# MelansonTech_Isolated_Shunt_Amplifier_re.net
KiCad netlist of a schematic drawn in Altium Designer
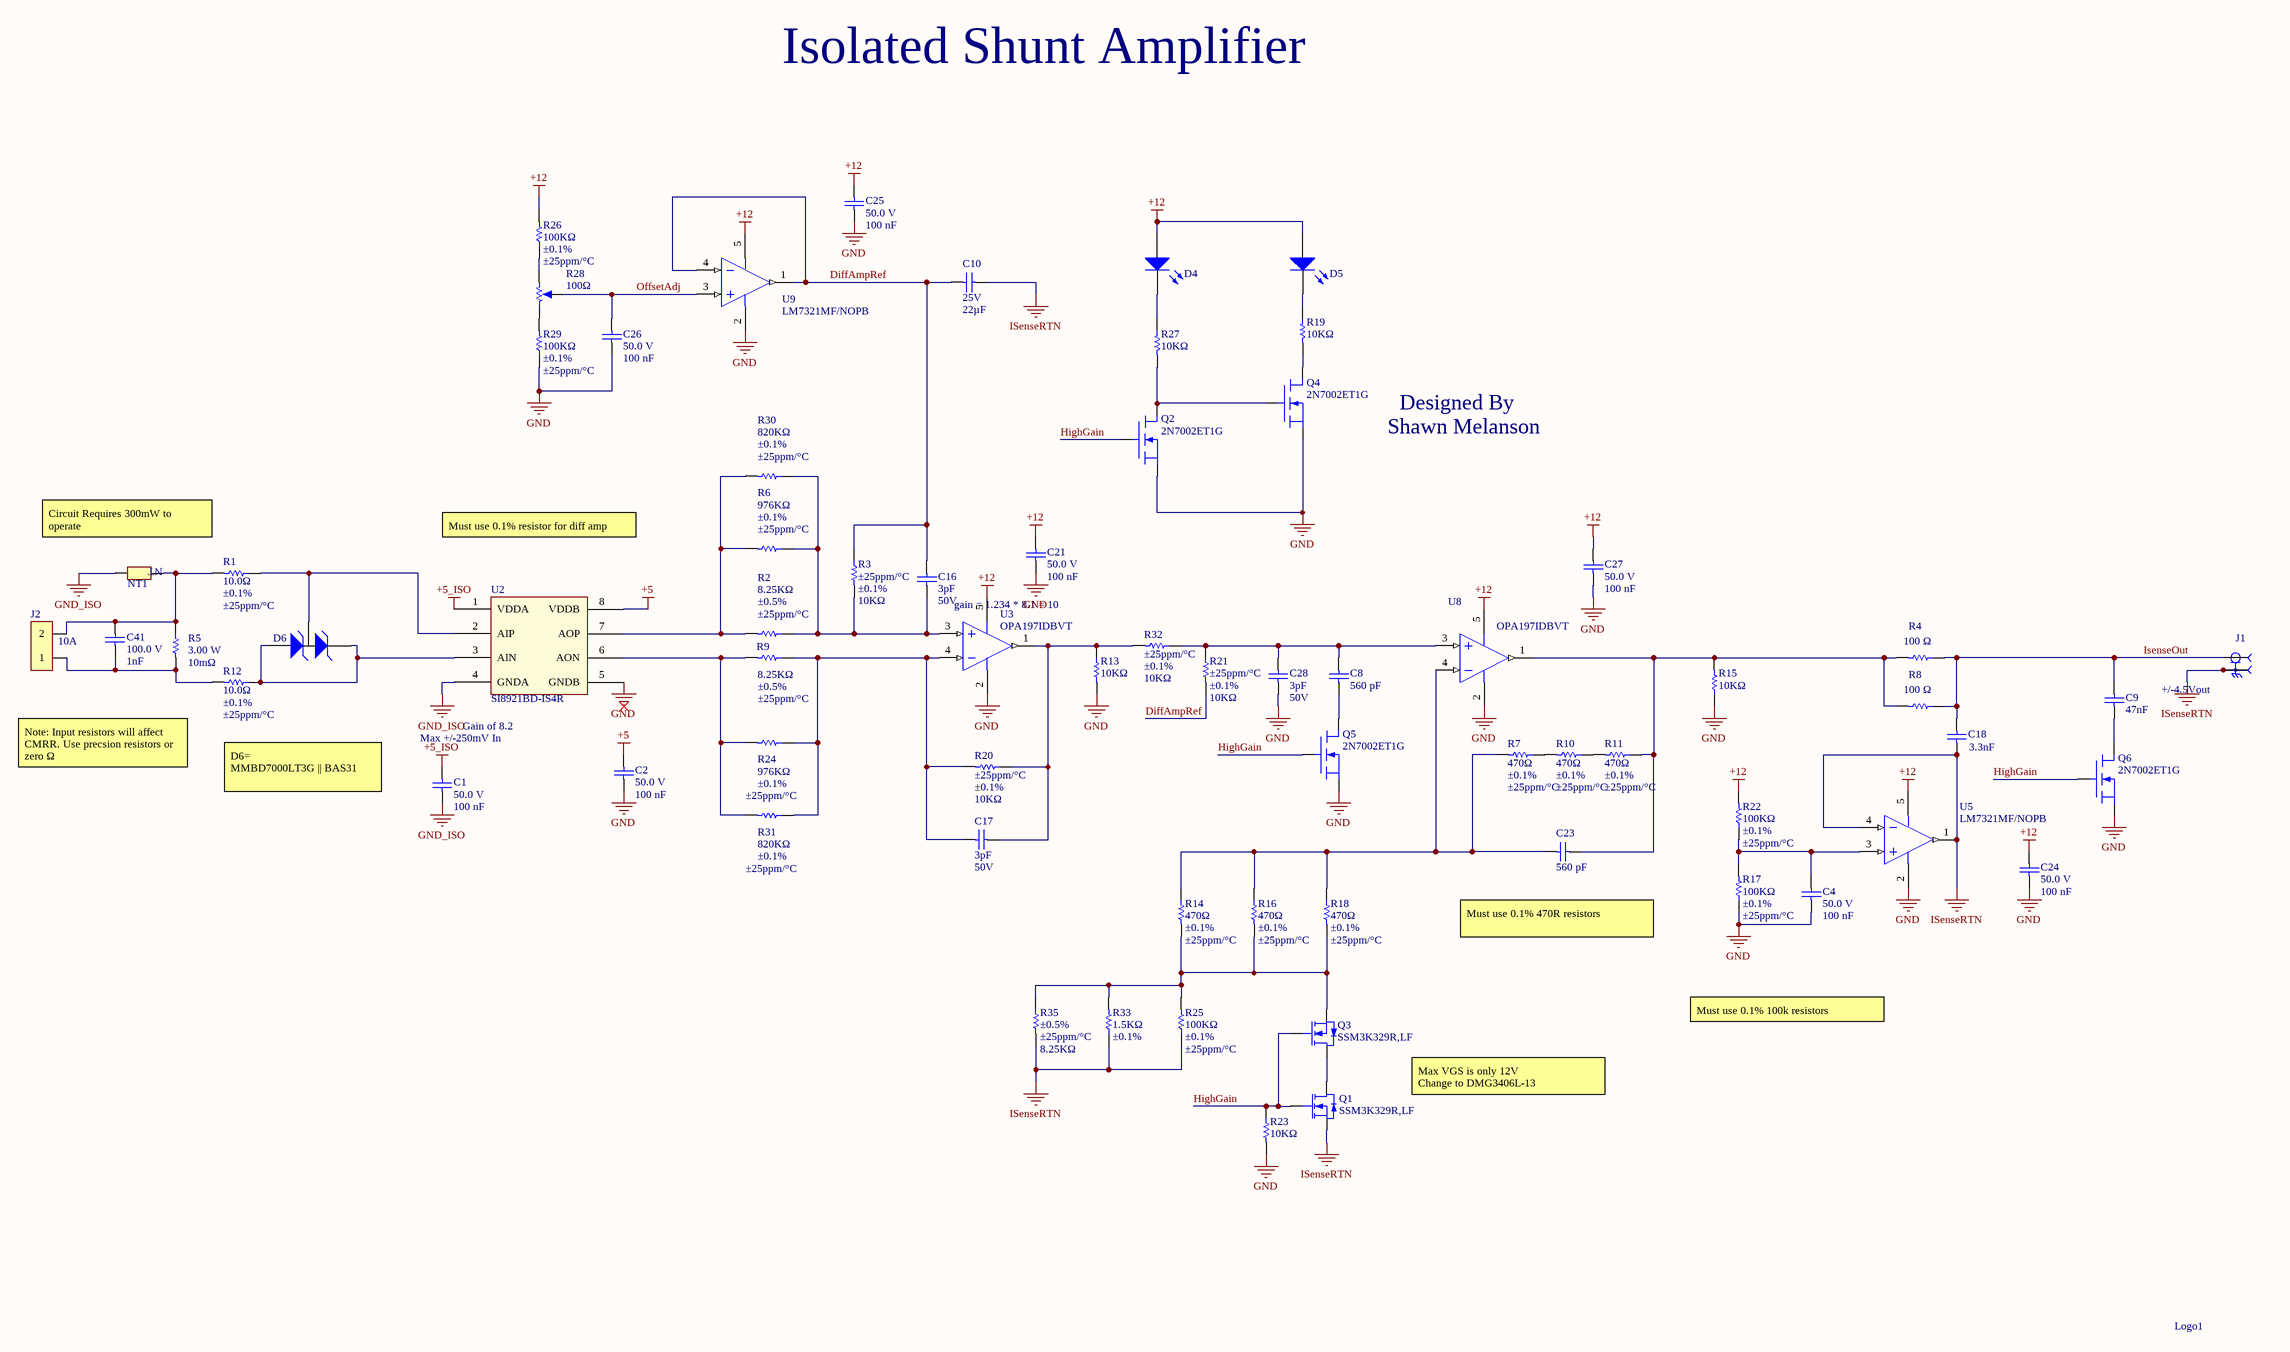
[diagram p0: MelansonTech Isolated Shunt Amplifier rev 2.SchDoc]

(export (version "E")
  (design (tool "Eeschema 10.0.6"))
  (components
    (comp (ref "C1")
      (value "CC0805KRX7R9BB104")
      (footprint "CAP, 0805, HD")
      (description "CAP CER 0.1UF 50V X7R 0805")
      (fields
        (field (name "VOLTAGE RATING (DC)") "50.0 V")
        (field (name "CAPACITANCE") "100 nF")
        (field (name "MANUFACTURER") "YAGEO")
      )
      (libsource (lib "Master Mar2024") (part "Cap,0805,100nf,50V,5%,CC0805KRX7R9BB104"))
    )
    (comp (ref "C2")
      (value "CC0805KRX7R9BB104")
      (footprint "CAP, 0805, HD")
      (description "CAP CER 0.1UF 50V X7R 0805")
      (fields
        (field (name "VOLTAGE RATING (DC)") "50.0 V")
        (field (name "CAPACITANCE") "100 nF")
        (field (name "MANUFACTURER") "YAGEO")
      )
      (libsource (lib "Master Mar2024") (part "Cap,0805,100nf,50V,5%,CC0805KRX7R9BB104"))
    )
    (comp (ref "C4")
      (value "CC0805KRX7R9BB104")
      (footprint "CAP, 0805, HD")
      (description "CAP CER 0.1UF 50V X7R 0805")
      (fields
        (field (name "VOLTAGE RATING (DC)") "50.0 V")
        (field (name "CAPACITANCE") "100 nF")
        (field (name "MANUFACTURER") "YAGEO")
      )
      (libsource (lib "Master Mar2024") (part "Cap,0805,100nf,50V,5%,CC0805KRX7R9BB104"))
    )
    (comp (ref "C8")
      (value "CC0805JRNPO9BN561")
      (footprint "CAP, 0805, HD")
      (description "CAP CER 560PF 50V C0G/NPO 0805")
      (fields
        (field (name "MFR") "YAGEO")
        (field (name "TOLERANCE") "±5%")
        (field (name "CAPACITANCE") "560 pF")
      )
      (libsource (lib "Master Mar2024") (part "Cap,0805,560pF,50V,±5%,C0G,NP0,CC0805JRNPO9BN561"))
    )
    (comp (ref "C9")
      (value "CL21B473KCFNNNE")
      (footprint "CAP, 0805, HD")
      (description "CAP CER 0.047UF 100V X7R 0805")
      (fields
        (field (name "MANUFACTURER") "Samsung Electro-Mechanics")
        (field (name "TOLERANCE") "±10%")
        (field (name "CAPACITANCE") "47nF")
      )
      (libsource (lib "Master Mar2024") (part "Cap,0805,47nF,100V,±10%,CL21B473KCFNNNE"))
    )
    (comp (ref "C10")
      (value "CL21A226MAQNNNE")
      (footprint "Cap,0805")
      (description "CAP CER 22UF 25V X5R 0805")
      (fields
        (field (name "MANUFACTURER") "Samsung Electro-Mechanics")
        (field (name "TOLERANCE") "±20%")
        (field (name "VOLTAGE - RATED") "25V")
        (field (name "CAPACITANCE") "22µF")
      )
      (libsource (lib "Master Mar2024") (part "Cap,0805,22uF,25V,X5R,±20%,CL21A226MAQNNNE"))
    )
    (comp (ref "C16")
      (value "CC0805CRNPO9BN3R0")
      (footprint "CAP, 0805, HD")
      (description "CAP CER 3PF 50V C0G/NPO 0805")
      (fields
        (field (name "MANUFACTURER") "YAGEO")
        (field (name "TOLERANCE") "±0.25pF")
        (field (name "CAPACITANCE") "3pF")
        (field (name "VOLTAGE - RATED") "50V")
      )
      (libsource (lib "Master Mar2024") (part "CAP,0805,3pF,COG,NPO,CC0805CRNPO9BN3R0"))
    )
    (comp (ref "C17")
      (value "CC0805CRNPO9BN3R0")
      (footprint "CAP, 0805, HD")
      (description "CAP CER 3PF 50V C0G/NPO 0805")
      (fields
        (field (name "MANUFACTURER") "YAGEO")
        (field (name "TOLERANCE") "±0.25pF")
        (field (name "CAPACITANCE") "3pF")
        (field (name "VOLTAGE - RATED") "50V")
      )
      (libsource (lib "Master Mar2024") (part "CAP,0805,3pF,COG,NPO,CC0805CRNPO9BN3R0"))
    )
    (comp (ref "C18")
      (value "CC0805KPX7R9BB332")
      (footprint "CAP, 0805, HD")
      (description "CAP CER 3300PF 50V X7R 0805")
      (fields
        (field (name "MANUFACTURER") "YAGEO")
        (field (name "TOLERANCE") "±10%")
        (field (name "CAPACITANCE") "3.3nF")
      )
      (libsource (lib "Master Mar2024") (part "Cap,0805,3.3nF,50V,±10%,CC0805KPX7R9BB332"))
    )
    (comp (ref "C21")
      (value "CC0805KRX7R9BB104")
      (footprint "CAP, 0805, HD")
      (description "CAP CER 0.1UF 50V X7R 0805")
      (fields
        (field (name "VOLTAGE RATING (DC)") "50.0 V")
        (field (name "CAPACITANCE") "100 nF")
        (field (name "MANUFACTURER") "YAGEO")
      )
      (libsource (lib "Master Mar2024") (part "Cap,0805,100nf,50V,5%,CC0805KRX7R9BB104"))
    )
    (comp (ref "C23")
      (value "CC0805JRNPO9BN561")
      (footprint "Cap,0805")
      (description "CAP CER 560PF 50V C0G/NPO 0805")
      (fields
        (field (name "MFR") "YAGEO")
        (field (name "TOLERANCE") "±5%")
        (field (name "CAPACITANCE") "560 pF")
      )
      (libsource (lib "Master Mar2024") (part "Cap,0805,560pF,50V,±5%,C0G,NP0,CC0805JRNPO9BN561"))
    )
    (comp (ref "C24")
      (value "CC0805KRX7R9BB104")
      (footprint "CAP, 0805, HD")
      (description "CAP CER 0.1UF 50V X7R 0805")
      (fields
        (field (name "VOLTAGE RATING (DC)") "50.0 V")
        (field (name "CAPACITANCE") "100 nF")
        (field (name "MANUFACTURER") "YAGEO")
      )
      (libsource (lib "Master Mar2024") (part "Cap,0805,100nf,50V,5%,CC0805KRX7R9BB104"))
    )
    (comp (ref "C25")
      (value "CC0805KRX7R9BB104")
      (footprint "CAP, 0805, HD")
      (description "CAP CER 0.1UF 50V X7R 0805")
      (fields
        (field (name "VOLTAGE RATING (DC)") "50.0 V")
        (field (name "CAPACITANCE") "100 nF")
        (field (name "MANUFACTURER") "YAGEO")
      )
      (libsource (lib "Master Mar2024") (part "Cap,0805,100nf,50V,5%,CC0805KRX7R9BB104"))
    )
    (comp (ref "C26")
      (value "CC0805KRX7R9BB104")
      (footprint "CAP, 0805, HD")
      (description "CAP CER 0.1UF 50V X7R 0805")
      (fields
        (field (name "VOLTAGE RATING (DC)") "50.0 V")
        (field (name "CAPACITANCE") "100 nF")
        (field (name "MANUFACTURER") "YAGEO")
      )
      (libsource (lib "Master Mar2024") (part "Cap,0805,100nf,50V,5%,CC0805KRX7R9BB104"))
    )
    (comp (ref "C27")
      (value "CC0805KRX7R9BB104")
      (footprint "CAP, 0805, HD")
      (description "CAP CER 0.1UF 50V X7R 0805")
      (fields
        (field (name "VOLTAGE RATING (DC)") "50.0 V")
        (field (name "CAPACITANCE") "100 nF")
        (field (name "MANUFACTURER") "YAGEO")
      )
      (libsource (lib "Master Mar2024") (part "Cap,0805,100nf,50V,5%,CC0805KRX7R9BB104"))
    )
    (comp (ref "C28")
      (value "CC0805CRNPO9BN3R0")
      (footprint "CAP, 0805, HD")
      (description "CAP CER 3PF 50V C0G/NPO 0805")
      (fields
        (field (name "MANUFACTURER") "YAGEO")
        (field (name "TOLERANCE") "±0.25pF")
        (field (name "CAPACITANCE") "3pF")
        (field (name "VOLTAGE - RATED") "50V")
      )
      (libsource (lib "Master Mar2024") (part "CAP,0805,3pF,COG,NPO,CC0805CRNPO9BN3R0"))
    )
    (comp (ref "C41")
      (value "C0805X102J1GACAUTO")
      (footprint "CAP, 0805, HD")
      (description "CAPACITOR, 1NF, 100V, NP0, 0805")
      (fields (field (name "VOLTAGE RATING (DC)") "100.0 V") (field (name "CAPACITANCE") "1nF"))
      (libsource (lib "Master Nov2021") (part "Cap,0805,1nF,±5%,100Vdc,CL10F104ZB8NNNC"))
    )
    (comp (ref "D4")
      (value "OVLBB4C7")
      (footprint "LED,TH,T1,3MM-Vert")
      (description "Blue 470nm LED Indication - Discrete 3.2V Radial")
      (fields (field (name "MFG") "TT Electronics/Optek Technology"))
      (libsource (lib "Master Nov2021") (part "LED,TH,T1,3mm,Blue,OVLBB4C7"))
    )
    (comp (ref "D5")
      (value "OVLBB4C7")
      (footprint "LED,TH,T1,3MM-Vert")
      (description "Blue 470nm LED Indication - Discrete 3.2V Radial")
      (fields (field (name "MFG") "TT Electronics/Optek Technology"))
      (libsource (lib "Master Nov2021") (part "LED,TH,T1,3mm,Blue,OVLBB4C7"))
    )
    (comp (ref "D6")
      (value "BAT54SLT1G")
      (footprint "SOT23-3")
      (fields (field (name "BASE PART NUMBER") "BAT54SL") (field (name "MANUFACTURER") "ON Semiconductor"))
      (libsource (lib "Master Nov2021") (part "Diode,Shottky,Array,Series,30V,200mA,BAT54SLT1G"))
    )
    (comp (ref "J1")
      (value "142-0701-801")
      (footprint "CINCH_142-0701-801")
      (description "CONN SMA JACK STR 50OHM EDGE MNT")
      (fields (field (name "MANUFACTURER") "Cinch Connectivity Solutions Johnson"))
      (libsource (lib "Master JUL_2019-Shawn") (part "Conn,SMA,Female,End Launch,142-0701-801"))
    )
    (comp (ref "J2")
      (value "TE Connectivity 282836-2")
      (footprint "TERM BLOCK 2POS SIDE ENTRY 5MM")
      (description "Wire to Board 2 Position 5 mm Pitch 30-16 AWG Euro Style Terminal Block")
      (fields (field (name "MANUFACTURER PART NUMBER") "282836-2"))
      (libsource (lib "Master DEC 2020") (part "TERM BLOCK 2POS SIDE ENTRY 5MM, 282836-2"))
    )
    (comp (ref "Logo1")
      (value "Open Source Logo")
      (footprint "Symbol,Open Source - No Text")
      (description "Open Source Silk Screen Logo")
      (libsource (lib "Master Mar2024") (part "Symbol,Open Source"))
    )
    (comp (ref "NT1")
      (value "Net Tie,0.254mm")
      (footprint "0.254mm Net Tie")
      (libsource (lib "Master Mar2021") (part "Net Tie,0.254mm"))
    )
    (comp (ref "Q1")
      (value "SSM3K329R,LF")
      (footprint "SOT23-3")
      (description "N-Channel 30V 3.5A (Ta) 1W (Ta) Surface Mount SOT-23F")
      (fields (field (name "MFG P/N") "SSM3K329R,LF"))
      (libsource (lib "Master Mar2024") (part "MOSFET.N-Chan, SOT-23-3,3.5A,30V,1W,SSM3K329R,LF"))
    )
    (comp (ref "Q2")
      (value "2N7002ET1G")
      (footprint "SOT23-3")
      (description "Small Signal MOSFET, 60 V, 310 mA, Single, N-Channel, 3-Pin SOT-23, Pb-Free, Tape and Reel")
      (fields
        (field (name "MANUFACTURER") "ON Semiconductor")
        (field (name "MANUFACTURER PART NUMBER") "2N7002ET1G")
      )
      (libsource (lib "Master DEC 2020") (part "MOSFET,N-Channel,SOT23,0.25A,60V,2N7002ET1G"))
    )
    (comp (ref "Q3")
      (value "SSM3K329R,LF")
      (footprint "SOT23-3")
      (description "N-Channel 30V 3.5A (Ta) 1W (Ta) Surface Mount SOT-23F")
      (fields (field (name "MFG P/N") "SSM3K329R,LF"))
      (libsource (lib "Master Mar2024") (part "MOSFET.N-Chan, SOT-23-3,3.5A,30V,1W,SSM3K329R,LF"))
    )
    (comp (ref "Q4")
      (value "2N7002ET1G")
      (footprint "SOT23-3")
      (description "Small Signal MOSFET, 60 V, 310 mA, Single, N-Channel, 3-Pin SOT-23, Pb-Free, Tape and Reel")
      (fields
        (field (name "MANUFACTURER") "ON Semiconductor")
        (field (name "MANUFACTURER PART NUMBER") "2N7002ET1G")
      )
      (libsource (lib "Master DEC 2020") (part "MOSFET,N-Channel,SOT23,0.25A,60V,2N7002ET1G"))
    )
    (comp (ref "Q5")
      (value "2N7002ET1G")
      (footprint "SOT23-3")
      (description "Small Signal MOSFET, 60 V, 310 mA, Single, N-Channel, 3-Pin SOT-23, Pb-Free, Tape and Reel")
      (fields
        (field (name "MANUFACTURER") "ON Semiconductor")
        (field (name "MANUFACTURER PART NUMBER") "2N7002ET1G")
      )
      (libsource (lib "Master DEC 2020") (part "MOSFET,N-Channel,SOT23,0.25A,60V,2N7002ET1G"))
    )
    (comp (ref "Q6")
      (value "2N7002ET1G")
      (footprint "SOT23-3")
      (description "Small Signal MOSFET, 60 V, 310 mA, Single, N-Channel, 3-Pin SOT-23, Pb-Free, Tape and Reel")
      (fields
        (field (name "MANUFACTURER") "ON Semiconductor")
        (field (name "MANUFACTURER PART NUMBER") "2N7002ET1G")
      )
      (libsource (lib "Master DEC 2020") (part "MOSFET,N-Channel,SOT23,0.25A,60V,2N7002ET1G"))
    )
    (comp (ref "R1")
      (value "RNCS0805BKE10R0")
      (footprint "res, 0805, HD")
      (description "RES 10 OHM 0.1% 1/10W 0805")
      (fields
        (field (name "MANUFACTURER") "Stackpole Electronics Inc")
        (field (name "RESISTANCE") "10.0Ω")
        (field (name "TOLERANCE") "±0.1%")
        (field (name "TEMPERATURE COEFFICIENT") "±25ppm/°C")
      )
      (libsource (lib "Master Mar2024") (part "Res,0805,10.0Ω,0.1%,±25ppm/°C,0.1W,RNCS0805BKE10R0"))
    )
    (comp (ref "R2")
      (value "RR1220P-8251-D-M")
      (footprint "res, 0805, HD")
      (description "RES SMD 8.25KOHM 0.5% 1/10W 0805")
      (fields
        (field (name "MANUFACTURER") "Susumu")
        (field (name "TOLERANCE") "±0.5%")
        (field (name "TEMPERATURE COEFFICIENT") "±25ppm/°C")
        (field (name "RESISTANCE") "8.25KΩ")
      )
      (libsource (lib "Master Mar2024") (part "Res,0805,8.25KΩ,0.5%,±25ppm/°C,RR1220P-8251-D-M"))
    )
    (comp (ref "R3")
      (value "RG2012P-103-B-T5")
      (footprint "res, 0805, HD")
      (description "RES SMD 10K OHM 0.1% 1/8W 0805")
      (fields
        (field (name "MFR") "Susumu")
        (field (name "TEMPERATURE COEFFICIENT") "±25ppm/°C")
        (field (name "RESISTANCE TOLERANCE") "±0.1%")
        (field (name "RESISTANCE") "10KΩ")
      )
      (libsource (lib "Master Mar2024") (part "Res,0805,10.0kΩ,0.1%,±25ppm/°C,RG2012P-103-B-T5"))
    )
    (comp (ref "R4")
      (value "CRCW0805100RJNEAC")
      (footprint "res, 0805, HD")
      (description "RES 100 OHM 5% 1/8W 0805")
      (fields (field (name "TOLERANCE") "±5%") (field (name "RESISTANCE") "100 Ω"))
      (libsource (lib "Master Mar2024") (part "Res,0805,100Ω,5%,±200ppm/°C"))
    )
    (comp (ref "R5")
      (value "CRA2512-FZ-R010ELF")
      (footprint "Res 2512")
      (description "Resistor; Metal Film; Res 0.01 Ohms; Pwr-Rtg 3 W; Tol 1%; SMT; 2512; Current Sense")
      (fields (field (name "POWER RATING") "3.00 W") (field (name "RESISTANCE") "10mΩ"))
      (libsource (lib "Master Mar2024") (part "Res,2512,10mΩ,3.00W,±1%,CRA2512-FZ-R010ELF"))
    )
    (comp (ref "R6")
      (value "ERA-6AEB9763V")
      (footprint "res, 0805, HD")
      (description "RES SMD 976K OHM 0.1% 1/8W 0805")
      (fields
        (field (name "MANUFACTURER") "Panasonic Electronic Components")
        (field (name "RESISTANCE") "976KΩ")
        (field (name "TOLERANCE") "±0.1%")
        (field (name "TEMPERATURE COEFFICIENT") "±25ppm/°C")
      )
      (libsource (lib "Master Mar2024") (part "Res,0805,976KΩ,±0.1%,±25ppm/°C,ERA-6AEB9763V"))
    )
    (comp (ref "R7")
      (value "ERA-6AEB471V")
      (footprint "res, 0805, HD")
      (description "RES SMD 470 OHM 0.1% 1/8W 0805")
      (fields
        (field (name "MANUFACTURER") "Panasonic Electronic Components")
        (field (name "RESISTANCE") "470Ω")
        (field (name "TOLERANCE") "±0.1%")
        (field (name "TEMPERATURE COEFFICIENT") "±25ppm/°C")
      )
      (libsource (lib "Master Mar2024") (part "Res,0805,470Ω,±0.1%,±25ppm/°C,ERA-6AEB471V"))
    )
    (comp (ref "R8")
      (value "CRCW0805100RJNEAC")
      (footprint "res, 0805, HD")
      (description "RES 100 OHM 5% 1/8W 0805")
      (fields (field (name "TOLERANCE") "±5%") (field (name "RESISTANCE") "100 Ω"))
      (libsource (lib "Master Mar2024") (part "Res,0805,100Ω,5%,±200ppm/°C"))
    )
    (comp (ref "R9")
      (value "RR1220P-8251-D-M")
      (footprint "res, 0805, HD")
      (description "RES SMD 8.25KOHM 0.5% 1/10W 0805")
      (fields
        (field (name "MANUFACTURER") "Susumu")
        (field (name "TOLERANCE") "±0.5%")
        (field (name "TEMPERATURE COEFFICIENT") "±25ppm/°C")
        (field (name "RESISTANCE") "8.25KΩ")
      )
      (libsource (lib "Master Mar2024") (part "Res,0805,8.25KΩ,0.5%,±25ppm/°C,RR1220P-8251-D-M"))
    )
    (comp (ref "R10")
      (value "ERA-6AEB471V")
      (footprint "res, 0805, HD")
      (description "RES SMD 470 OHM 0.1% 1/8W 0805")
      (fields
        (field (name "MANUFACTURER") "Panasonic Electronic Components")
        (field (name "RESISTANCE") "470Ω")
        (field (name "TOLERANCE") "±0.1%")
        (field (name "TEMPERATURE COEFFICIENT") "±25ppm/°C")
      )
      (libsource (lib "Master Mar2024") (part "Res,0805,470Ω,±0.1%,±25ppm/°C,ERA-6AEB471V"))
    )
    (comp (ref "R11")
      (value "ERA-6AEB471V")
      (footprint "res, 0805, HD")
      (description "RES SMD 470 OHM 0.1% 1/8W 0805")
      (fields
        (field (name "MANUFACTURER") "Panasonic Electronic Components")
        (field (name "RESISTANCE") "470Ω")
        (field (name "TOLERANCE") "±0.1%")
        (field (name "TEMPERATURE COEFFICIENT") "±25ppm/°C")
      )
      (libsource (lib "Master Mar2024") (part "Res,0805,470Ω,±0.1%,±25ppm/°C,ERA-6AEB471V"))
    )
    (comp (ref "R12")
      (value "RNCS0805BKE10R0")
      (footprint "res, 0805, HD")
      (description "RES 10 OHM 0.1% 1/10W 0805")
      (fields
        (field (name "MANUFACTURER") "Stackpole Electronics Inc")
        (field (name "RESISTANCE") "10.0Ω")
        (field (name "TOLERANCE") "±0.1%")
        (field (name "TEMPERATURE COEFFICIENT") "±25ppm/°C")
      )
      (libsource (lib "Master Mar2024") (part "Res,0805,10.0Ω,0.1%,±25ppm/°C,0.1W,RNCS0805BKE10R0"))
    )
    (comp (ref "R13")
      (value "Vishay / Dale CRCW080510K0FKTA")
      (footprint "res, 0805, HD")
      (description "RES SMD 10K OHM 1% 1/8W 0805")
      (fields (field (name "RESISTANCE") "10KΩ"))
      (libsource (lib "Master DEC 2020") (part "Res,0805,10.0kΩ,1%,100 ppm,CRCW080510K0FKTA"))
    )
    (comp (ref "R14")
      (value "ERA-6AEB471V")
      (footprint "res, 0805, HD")
      (description "RES SMD 470 OHM 0.1% 1/8W 0805")
      (fields
        (field (name "MANUFACTURER") "Panasonic Electronic Components")
        (field (name "RESISTANCE") "470Ω")
        (field (name "TOLERANCE") "±0.1%")
        (field (name "TEMPERATURE COEFFICIENT") "±25ppm/°C")
      )
      (libsource (lib "Master Mar2024") (part "Res,0805,470Ω,±0.1%,±25ppm/°C,ERA-6AEB471V"))
    )
    (comp (ref "R15")
      (value "Vishay / Dale CRCW080510K0FKTA")
      (footprint "res, 0805, HD")
      (description "RES SMD 10K OHM 1% 1/8W 0805")
      (fields (field (name "RESISTANCE") "10KΩ"))
      (libsource (lib "Master JULY2019") (part "Res,0805,10.0kΩ,1%,100 ppm,CRCW080510K0FKTA"))
    )
    (comp (ref "R16")
      (value "ERA-6AEB471V")
      (footprint "res, 0805, HD")
      (description "RES SMD 470 OHM 0.1% 1/8W 0805")
      (fields
        (field (name "MANUFACTURER") "Panasonic Electronic Components")
        (field (name "RESISTANCE") "470Ω")
        (field (name "TOLERANCE") "±0.1%")
        (field (name "TEMPERATURE COEFFICIENT") "±25ppm/°C")
      )
      (libsource (lib "Master Mar2024") (part "Res,0805,470Ω,±0.1%,±25ppm/°C,ERA-6AEB471V"))
    )
    (comp (ref "R17")
      (value "ERA-6AEB104V")
      (footprint "res, 0805, HD")
      (description "RES SMD 100K OHM 0.1% 1/8W 0805")
      (fields
        (field (name "MANUFACTURER") "Panasonic Electronic Components")
        (field (name "RESISTANCE") "100KΩ")
        (field (name "TOLERANCE") "±0.1%")
        (field (name "TEMPERATURE COEFFICIENT") "±25ppm/°C")
      )
      (libsource (lib "Master Mar2024") (part "Res,0805,100K,±0.1%,±25ppm/°C,ERA-6AEB104V"))
    )
    (comp (ref "R18")
      (value "ERA-6AEB471V")
      (footprint "res, 0805, HD")
      (description "RES SMD 470 OHM 0.1% 1/8W 0805")
      (fields
        (field (name "MANUFACTURER") "Panasonic Electronic Components")
        (field (name "RESISTANCE") "470Ω")
        (field (name "TOLERANCE") "±0.1%")
        (field (name "TEMPERATURE COEFFICIENT") "±25ppm/°C")
      )
      (libsource (lib "Master Mar2024") (part "Res,0805,470Ω,±0.1%,±25ppm/°C,ERA-6AEB471V"))
    )
    (comp (ref "R19")
      (value "Vishay / Dale CRCW080510K0FKTA")
      (footprint "res, 0805, HD")
      (description "RES SMD 10K OHM 1% 1/8W 0805")
      (fields (field (name "RESISTANCE") "10KΩ"))
      (libsource (lib "Master JULY2019") (part "Res,0805,10.0kΩ,1%,100 ppm,CRCW080510K0FKTA"))
    )
    (comp (ref "R20")
      (value "RG2012P-103-B-T5")
      (footprint "res, 0805, HD")
      (description "RES SMD 10K OHM 0.1% 1/8W 0805")
      (fields
        (field (name "MFR") "Susumu")
        (field (name "TEMPERATURE COEFFICIENT") "±25ppm/°C")
        (field (name "RESISTANCE TOLERANCE") "±0.1%")
        (field (name "RESISTANCE") "10KΩ")
      )
      (libsource (lib "Master Mar2024") (part "Res,0805,10.0kΩ,0.1%,±25ppm/°C,RG2012P-103-B-T5"))
    )
    (comp (ref "R21")
      (value "RG2012P-103-B-T5")
      (footprint "res, 0805, HD")
      (description "RES SMD 10K OHM 0.1% 1/8W 0805")
      (fields
        (field (name "MFR") "Susumu")
        (field (name "TEMPERATURE COEFFICIENT") "±25ppm/°C")
        (field (name "RESISTANCE TOLERANCE") "±0.1%")
        (field (name "RESISTANCE") "10KΩ")
      )
      (libsource (lib "Master Mar2024") (part "Res,0805,10.0kΩ,0.1%,±25ppm/°C,RG2012P-103-B-T5"))
    )
    (comp (ref "R22")
      (value "ERA-6AEB104V")
      (footprint "res, 0805, HD")
      (description "RES SMD 100K OHM 0.1% 1/8W 0805")
      (fields
        (field (name "MANUFACTURER") "Panasonic Electronic Components")
        (field (name "RESISTANCE") "100KΩ")
        (field (name "TOLERANCE") "±0.1%")
        (field (name "TEMPERATURE COEFFICIENT") "±25ppm/°C")
      )
      (libsource (lib "Master Mar2024") (part "Res,0805,100K,±0.1%,±25ppm/°C,ERA-6AEB104V"))
    )
    (comp (ref "R23")
      (value "Vishay / Dale CRCW080510K0FKTA")
      (footprint "res, 0805, HD")
      (description "RES SMD 10K OHM 1% 1/8W 0805")
      (fields (field (name "RESISTANCE") "10KΩ"))
      (libsource (lib "Master JULY2019") (part "Res,0805,10.0kΩ,1%,100 ppm,CRCW080510K0FKTA"))
    )
    (comp (ref "R24")
      (value "ERA-6AEB9763V")
      (footprint "res, 0805, HD")
      (description "RES SMD 976K OHM 0.1% 1/8W 0805")
      (fields
        (field (name "MANUFACTURER") "Panasonic Electronic Components")
        (field (name "RESISTANCE") "976KΩ")
        (field (name "TOLERANCE") "±0.1%")
        (field (name "TEMPERATURE COEFFICIENT") "±25ppm/°C")
      )
      (libsource (lib "Master Mar2024") (part "Res,0805,976KΩ,±0.1%,±25ppm/°C,ERA-6AEB9763V"))
    )
    (comp (ref "R25")
      (value "ERA-6AEB104V")
      (footprint "res, 0805, HD")
      (description "RES SMD 100K OHM 0.1% 1/8W 0805")
      (fields
        (field (name "MANUFACTURER") "Panasonic Electronic Components")
        (field (name "RESISTANCE") "100KΩ")
        (field (name "TOLERANCE") "±0.1%")
        (field (name "TEMPERATURE COEFFICIENT") "±25ppm/°C")
      )
      (libsource (lib "Master Mar2024") (part "Res,0805,100K,±0.1%,±25ppm/°C,ERA-6AEB104V"))
    )
    (comp (ref "R26")
      (value "ERA-6AEB104V")
      (footprint "res, 0805, HD")
      (description "RES SMD 100K OHM 0.1% 1/8W 0805")
      (fields
        (field (name "MANUFACTURER") "Panasonic Electronic Components")
        (field (name "RESISTANCE") "100KΩ")
        (field (name "TOLERANCE") "±0.1%")
        (field (name "TEMPERATURE COEFFICIENT") "±25ppm/°C")
      )
      (libsource (lib "Master Mar2024") (part "Res,0805,100K,±0.1%,±25ppm/°C,ERA-6AEB104V"))
    )
    (comp (ref "R27")
      (value "Vishay / Dale CRCW080510K0FKTA")
      (footprint "res, 0805, HD")
      (description "RES SMD 10K OHM 1% 1/8W 0805")
      (fields (field (name "RESISTANCE") "10KΩ"))
      (libsource (lib "Master JULY2019") (part "Res,0805,10.0kΩ,1%,100 ppm,CRCW080510K0FKTA"))
    )
    (comp (ref "R28")
      (value "TC33X-2-101E")
      (footprint "Res,SMD,POT,TC33 Series")
      (description "TRIMMER 100 OHM 0.1W J LEAD TOP")
      (fields
        (field (name "MANUFACTURER") "Bourns Inc.")
        (field (name "TOLERANCE") "±25%")
        (field (name "RESISTANCE") "100Ω")
      )
      (libsource (lib "Master Nov2021") (part "Res,POT,SMD,100Ω,0.1W, TC33X-2-101E"))
    )
    (comp (ref "R29")
      (value "ERA-6AEB104V")
      (footprint "res, 0805, HD")
      (description "RES SMD 100K OHM 0.1% 1/8W 0805")
      (fields
        (field (name "MANUFACTURER") "Panasonic Electronic Components")
        (field (name "RESISTANCE") "100KΩ")
        (field (name "TOLERANCE") "±0.1%")
        (field (name "TEMPERATURE COEFFICIENT") "±25ppm/°C")
      )
      (libsource (lib "Master Mar2024") (part "Res,0805,100K,±0.1%,±25ppm/°C,ERA-6AEB104V"))
    )
    (comp (ref "R30")
      (value "RG2012P-824-D-T5")
      (footprint "res, 0805, HD")
      (description "RES SMD 820K OHM 0.5% 1/8W 0805")
      (fields
        (field (name "MANUFACTURER") "Susumu")
        (field (name "RESISTANCE") "820KΩ")
        (field (name "TOLERANCE") "±0.1%")
        (field (name "TEMPERATURE COEFFICIENT") "±25ppm/°C")
      )
      (libsource (lib "Master Mar2024") (part "Res,0805,820KΩ,±0.1%,±25ppm/°C,RG2012P-824-D-T5"))
    )
    (comp (ref "R31")
      (value "RG2012P-824-D-T5")
      (footprint "res, 0805, HD")
      (description "RES SMD 820K OHM 0.5% 1/8W 0805")
      (fields
        (field (name "MANUFACTURER") "Susumu")
        (field (name "RESISTANCE") "820KΩ")
        (field (name "TOLERANCE") "±0.1%")
        (field (name "TEMPERATURE COEFFICIENT") "±25ppm/°C")
      )
      (libsource (lib "Master Mar2024") (part "Res,0805,820KΩ,±0.1%,±25ppm/°C,RG2012P-824-D-T5"))
    )
    (comp (ref "R32")
      (value "RG2012P-103-B-T5")
      (footprint "res, 0805, HD")
      (description "RES SMD 10K OHM 0.1% 1/8W 0805")
      (fields
        (field (name "MFR") "Susumu")
        (field (name "TEMPERATURE COEFFICIENT") "±25ppm/°C")
        (field (name "RESISTANCE TOLERANCE") "±0.1%")
        (field (name "RESISTANCE") "10KΩ")
      )
      (libsource (lib "Master Mar2024") (part "Res,0805,10.0kΩ,0.1%,±25ppm/°C,RG2012P-103-B-T5"))
    )
    (comp (ref "R33")
      (value "RG2012P-152-B-T5")
      (footprint "res, 0805, HD")
      (description "RES SMD 1.5K OHM 0.1% 1/8W 0805")
      (fields
        (field (name "MANUFACTURER") "Susumu")
        (field (name "RESISTANCE") "1.5KΩ")
        (field (name "TOLERANCE") "±0.1%")
      )
      (libsource (lib "Master Mar2024") (part "Res,0805,1.5KΩ,0.1%,±25ppm/°C,RG2012P-152-B-T5"))
    )
    (comp (ref "R35")
      (value "RR1220P-8251-D-M")
      (footprint "res, 0805, HD")
      (description "RES SMD 8.25KOHM 0.5% 1/10W 0805")
      (fields
        (field (name "MANUFACTURER") "Susumu")
        (field (name "TOLERANCE") "±0.5%")
        (field (name "TEMPERATURE COEFFICIENT") "±25ppm/°C")
        (field (name "RESISTANCE") "8.25KΩ")
      )
      (libsource (lib "Master Mar2024") (part "Res,0805,8.25KΩ,0.5%,±25ppm/°C,RR1220P-8251-D-M"))
    )
    (comp (ref "U2")
      (value "SI8921BD-IS4R")
      (footprint "SOIC-8 DWV")
      (description "Isolation IC Inverters, Power Supplies, UPS 8-SOIC")
      (fields (field (name "MFR") "Skyworks Solutions Inc."))
      (libsource (lib "Master Mar2024") (part "IC,CurrentSense,Isolated,8.2 Gain,500Khz,SI8921BD-IS4R"))
    )
    (comp (ref "U3")
      (value "OPA197IDBVT")
      (footprint "SOT23-5")
      (description "General Purpose Amplifier 1 Circuit Rail-to-Rail SOT-23-5")
      (fields (field (name "MANUFACTURER") "Texas Instruments") (field (name "MFG P/N") "OPA197IDBVT"))
      (libsource (lib "Master JULY2019") (part "OPAMP, single, General Purpose,Rail-to-Rail,10MHz,SOT-23-5,OPA197IDBVT"))
    )
    (comp (ref "U5")
      (value "LM7321MF/NOPB")
      (footprint "SOT23-5")
      (libsource (lib "Master Mar2024") (part "OPAMP,20Mhz,MOSFET DRIVER,SOT23-5,LM7321MF"))
    )
    (comp (ref "U8")
      (value "OPA197IDBVT")
      (footprint "SOT23-5")
      (description "General Purpose Amplifier 1 Circuit Rail-to-Rail SOT-23-5")
      (fields (field (name "MANUFACTURER") "Texas Instruments") (field (name "MFG P/N") "OPA197IDBVT"))
      (libsource (lib "Master JULY2019") (part "OPAMP, single, General Purpose,Rail-to-Rail,10MHz,SOT-23-5,OPA197IDBVT"))
    )
    (comp (ref "U9")
      (value "LM7321MF/NOPB")
      (footprint "SOT23-5")
      (libsource (lib "Master Mar2024") (part "OPAMP,20Mhz,MOSFET DRIVER,SOT23-5,LM7321MF"))
    )
  )
  (nets
    (net (code "1") (name "+5") (class "Default")
      (node (ref "C2") (pin "2") (pinfunction "2_2") (pintype "passive"))
      (node (ref "U2") (pin "8") (pinfunction "VDDB_8") (pintype "passive"))
    )
    (net (code "2") (name "+5_ISO") (class "Default")
      (node (ref "C1") (pin "2") (pinfunction "2_2") (pintype "passive"))
      (node (ref "U2") (pin "1") (pinfunction "VDDA_1") (pintype "passive"))
    )
    (net (code "3") (name "+12") (class "Default")
      (node (ref "C21") (pin "2") (pinfunction "2_2") (pintype "passive"))
      (node (ref "C24") (pin "2") (pinfunction "2_2") (pintype "passive"))
      (node (ref "C25") (pin "2") (pinfunction "2_2") (pintype "passive"))
      (node (ref "C27") (pin "2") (pinfunction "2_2") (pintype "passive"))
      (node (ref "D4") (pin "1") (pinfunction "A_1") (pintype "passive"))
      (node (ref "D5") (pin "1") (pinfunction "A_1") (pintype "passive"))
      (node (ref "R22") (pin "2") (pinfunction "2_2") (pintype "passive"))
      (node (ref "R26") (pin "2") (pinfunction "2_2") (pintype "passive"))
      (node (ref "U3") (pin "5") (pinfunction "V+_5") (pintype "power_in"))
      (node (ref "U5") (pin "5") (pinfunction "V+_5") (pintype "power_in"))
      (node (ref "U8") (pin "5") (pinfunction "V+_5") (pintype "power_in"))
      (node (ref "U9") (pin "5") (pinfunction "V+_5") (pintype "power_in"))
    )
    (net (code "4") (name "/DiffAmpRef") (class "Default")
      (node (ref "C10") (pin "2") (pinfunction "2_2") (pintype "passive"))
      (node (ref "C16") (pin "1") (pinfunction "1_1") (pintype "passive"))
      (node (ref "R21") (pin "2") (pinfunction "2_2") (pintype "passive"))
      (node (ref "R3") (pin "1") (pinfunction "1_1") (pintype "passive"))
      (node (ref "U9") (pin "1") (pinfunction "OUT_1") (pintype "output"))
      (node (ref "U9") (pin "4") (pinfunction "IN-_4") (pintype "input"))
    )
    (net (code "5") (name "/HighGain") (class "Default")
      (node (ref "Q1") (pin "1") (pinfunction "G_1") (pintype "passive"))
      (node (ref "Q2") (pin "1") (pinfunction "G_1") (pintype "passive"))
      (node (ref "Q3") (pin "1") (pinfunction "G_1") (pintype "passive"))
      (node (ref "Q5") (pin "1") (pinfunction "G_1") (pintype "passive"))
      (node (ref "Q6") (pin "1") (pinfunction "G_1") (pintype "passive"))
      (node (ref "R23") (pin "1") (pinfunction "1_1") (pintype "passive"))
    )
    (net (code "6") (name "/IsenseOut") (class "Default")
      (node (ref "C18") (pin "2") (pinfunction "2_2") (pintype "passive"))
      (node (ref "C9") (pin "2") (pinfunction "2_2") (pintype "passive"))
      (node (ref "J1") (pin "1") (pinfunction "1_1") (pintype "passive"))
      (node (ref "R4") (pin "1") (pinfunction "1_1") (pintype "passive"))
      (node (ref "R8") (pin "1") (pinfunction "1_1") (pintype "passive"))
    )
    (net (code "7") (name "/OffsetAdj") (class "Default")
      (node (ref "C26") (pin "2") (pinfunction "2_2") (pintype "passive"))
      (node (ref "R28") (pin "2") (pinfunction "2_2") (pintype "passive"))
      (node (ref "U9") (pin "3") (pinfunction "IN+_3") (pintype "input"))
    )
    (net (code "8") (name "GND") (class "Default")
      (node (ref "C2") (pin "1") (pinfunction "1_1") (pintype "passive"))
      (node (ref "C21") (pin "1") (pinfunction "1_1") (pintype "passive"))
      (node (ref "C24") (pin "1") (pinfunction "1_1") (pintype "passive"))
      (node (ref "C25") (pin "1") (pinfunction "1_1") (pintype "passive"))
      (node (ref "C26") (pin "1") (pinfunction "1_1") (pintype "passive"))
      (node (ref "C27") (pin "1") (pinfunction "1_1") (pintype "passive"))
      (node (ref "C28") (pin "1") (pinfunction "1_1") (pintype "passive"))
      (node (ref "C4") (pin "1") (pinfunction "1_1") (pintype "passive"))
      (node (ref "Q2") (pin "2") (pinfunction "S_2") (pintype "passive"))
      (node (ref "Q4") (pin "2") (pinfunction "S_2") (pintype "passive"))
      (node (ref "Q5") (pin "2") (pinfunction "S_2") (pintype "passive"))
      (node (ref "Q6") (pin "2") (pinfunction "S_2") (pintype "passive"))
      (node (ref "R13") (pin "2") (pinfunction "2_2") (pintype "passive"))
      (node (ref "R15") (pin "1") (pinfunction "1_1") (pintype "passive"))
      (node (ref "R17") (pin "1") (pinfunction "1_1") (pintype "passive"))
      (node (ref "R23") (pin "2") (pinfunction "2_2") (pintype "passive"))
      (node (ref "R29") (pin "1") (pinfunction "1_1") (pintype "passive"))
      (node (ref "U2") (pin "5") (pinfunction "GNDB_5") (pintype "passive"))
      (node (ref "U3") (pin "2") (pinfunction "V-_2") (pintype "power_in"))
      (node (ref "U5") (pin "2") (pinfunction "V-_2") (pintype "power_in"))
      (node (ref "U8") (pin "2") (pinfunction "V-_2") (pintype "power_in"))
      (node (ref "U9") (pin "2") (pinfunction "V-_2") (pintype "power_in"))
    )
    (net (code "9") (name "GND_ISO") (class "Default")
      (node (ref "C1") (pin "1") (pinfunction "1_1") (pintype "passive"))
      (node (ref "NT1") (pin "2") (pinfunction "2_2") (pintype "passive"))
      (node (ref "U2") (pin "4") (pinfunction "GNDA_4") (pintype "passive"))
    )
    (net (code "10") (name "ISenseRTN") (class "Default")
      (node (ref "C10") (pin "1") (pinfunction "1_1") (pintype "passive"))
      (node (ref "C18") (pin "1") (pinfunction "1_1") (pintype "passive"))
      (node (ref "J1") (pin "S1") (pinfunction "2_S1") (pintype "passive"))
      (node (ref "J1") (pin "S2") (pinfunction "2_S2") (pintype "passive"))
      (node (ref "J1") (pin "S3") (pinfunction "2_S3") (pintype "passive"))
      (node (ref "J1") (pin "S4") (pinfunction "2_S4") (pintype "passive"))
      (node (ref "Q1") (pin "2") (pinfunction "S_2") (pintype "passive"))
      (node (ref "R25") (pin "1") (pinfunction "1_1") (pintype "passive"))
      (node (ref "R33") (pin "1") (pinfunction "1_1") (pintype "passive"))
      (node (ref "R35") (pin "2") (pinfunction "2_2") (pintype "passive"))
      (node (ref "U5") (pin "1") (pinfunction "OUT_1") (pintype "output"))
      (node (ref "U5") (pin "4") (pinfunction "IN-_4") (pintype "input"))
    )
    (net (code "11") (name "Net-(C41-Pad1)") (class "Default")
      (node (ref "C41") (pin "1") (pinfunction "1_1") (pintype "passive"))
      (node (ref "J2") (pin "1") (pinfunction "1_1") (pintype "passive"))
      (node (ref "R12") (pin "2") (pinfunction "2_2") (pintype "passive"))
      (node (ref "R5") (pin "2") (pinfunction "2_2") (pintype "passive"))
    )
    (net (code "12") (name "Net-(C41-Pad2)") (class "Default")
      (node (ref "C41") (pin "2") (pinfunction "2_2") (pintype "passive"))
      (node (ref "J2") (pin "2") (pinfunction "2_2") (pintype "passive"))
      (node (ref "NT1") (pin "1") (pinfunction "1_1") (pintype "passive"))
      (node (ref "R1") (pin "2") (pinfunction "2_2") (pintype "passive"))
      (node (ref "R5") (pin "1") (pinfunction "1_1") (pintype "passive"))
    )
    (net (code "13") (name "Net-(D4-K)") (class "Default")
      (node (ref "D4") (pin "2") (pinfunction "K_2") (pintype "passive"))
      (node (ref "R27") (pin "1") (pinfunction "1_1") (pintype "passive"))
    )
    (net (code "14") (name "Net-(D5-K)") (class "Default")
      (node (ref "D5") (pin "2") (pinfunction "K_2") (pintype "passive"))
      (node (ref "R19") (pin "1") (pinfunction "1_1") (pintype "passive"))
    )
    (net (code "15") (name "Net-(D6-A)") (class "Default")
      (node (ref "D6") (pin "1") (pinfunction "A_1") (pintype "passive"))
      (node (ref "D6") (pin "2") (pinfunction "K_2") (pintype "passive"))
      (node (ref "R12") (pin "1") (pinfunction "1_1") (pintype "passive"))
      (node (ref "U2") (pin "3") (pinfunction "AIN_3") (pintype "passive"))
    )
    (net (code "16") (name "Net-(D6-AK)") (class "Default")
      (node (ref "D6") (pin "3") (pinfunction "AK_3") (pintype "passive"))
      (node (ref "R1") (pin "1") (pinfunction "1_1") (pintype "passive"))
      (node (ref "U2") (pin "2") (pinfunction "AIP_2") (pintype "passive"))
    )
    (net (code "17") (name "Net-(Q1-D)") (class "Default")
      (node (ref "Q1") (pin "3") (pinfunction "D_3") (pintype "passive"))
      (node (ref "Q3") (pin "3") (pinfunction "D_3") (pintype "passive"))
    )
    (net (code "18") (name "Net-(Q2-D)") (class "Default")
      (node (ref "Q2") (pin "3") (pinfunction "D_3") (pintype "passive"))
      (node (ref "Q4") (pin "1") (pinfunction "G_1") (pintype "passive"))
      (node (ref "R27") (pin "2") (pinfunction "2_2") (pintype "passive"))
    )
    (net (code "19") (name "Net-(Q3-S)") (class "Default")
      (node (ref "Q3") (pin "2") (pinfunction "S_2") (pintype "passive"))
      (node (ref "R14") (pin "2") (pinfunction "2_2") (pintype "passive"))
      (node (ref "R16") (pin "2") (pinfunction "2_2") (pintype "passive"))
      (node (ref "R18") (pin "2") (pinfunction "2_2") (pintype "passive"))
      (node (ref "R25") (pin "2") (pinfunction "2_2") (pintype "passive"))
      (node (ref "R33") (pin "2") (pinfunction "2_2") (pintype "passive"))
      (node (ref "R35") (pin "1") (pinfunction "1_1") (pintype "passive"))
    )
    (net (code "20") (name "Net-(Q4-D)") (class "Default")
      (node (ref "Q4") (pin "3") (pinfunction "D_3") (pintype "passive"))
      (node (ref "R19") (pin "2") (pinfunction "2_2") (pintype "passive"))
    )
    (net (code "21") (name "Net-(Q5-D)") (class "Default")
      (node (ref "C8") (pin "1") (pinfunction "1_1") (pintype "passive"))
      (node (ref "Q5") (pin "3") (pinfunction "D_3") (pintype "passive"))
    )
    (net (code "22") (name "Net-(Q6-D)") (class "Default")
      (node (ref "C9") (pin "1") (pinfunction "1_1") (pintype "passive"))
      (node (ref "Q6") (pin "3") (pinfunction "D_3") (pintype "passive"))
    )
    (net (code "23") (name "Net-(R10-Pad1)") (class "Default")
      (node (ref "R10") (pin "1") (pinfunction "1_1") (pintype "passive"))
      (node (ref "R11") (pin "2") (pinfunction "2_2") (pintype "passive"))
    )
    (net (code "24") (name "Net-(R10-Pad2)") (class "Default")
      (node (ref "R10") (pin "2") (pinfunction "2_2") (pintype "passive"))
      (node (ref "R7") (pin "1") (pinfunction "1_1") (pintype "passive"))
    )
    (net (code "25") (name "Net-(R26-Pad1)") (class "Default")
      (node (ref "R26") (pin "1") (pinfunction "1_1") (pintype "passive"))
      (node (ref "R28") (pin "3") (pinfunction "3_3") (pintype "passive"))
    )
    (net (code "26") (name "Net-(R28-Pad1)") (class "Default")
      (node (ref "R28") (pin "1") (pinfunction "1_1") (pintype "passive"))
      (node (ref "R29") (pin "2") (pinfunction "2_2") (pintype "passive"))
    )
    (net (code "27") (name "Net-(U2-AON)") (class "Default")
      (node (ref "R24") (pin "2") (pinfunction "2_2") (pintype "passive"))
      (node (ref "R31") (pin "2") (pinfunction "2_2") (pintype "passive"))
      (node (ref "R9") (pin "2") (pinfunction "2_2") (pintype "passive"))
      (node (ref "U2") (pin "6") (pinfunction "AON_6") (pintype "passive"))
    )
    (net (code "28") (name "Net-(U2-AOP)") (class "Default")
      (node (ref "R2") (pin "2") (pinfunction "2_2") (pintype "passive"))
      (node (ref "R30") (pin "2") (pinfunction "2_2") (pintype "passive"))
      (node (ref "R6") (pin "2") (pinfunction "2_2") (pintype "passive"))
      (node (ref "U2") (pin "7") (pinfunction "AOP_7") (pintype "passive"))
    )
    (net (code "29") (name "Net-(U3-1IN+)") (class "Default")
      (node (ref "C16") (pin "2") (pinfunction "2_2") (pintype "passive"))
      (node (ref "R2") (pin "1") (pinfunction "1_1") (pintype "passive"))
      (node (ref "R3") (pin "2") (pinfunction "2_2") (pintype "passive"))
      (node (ref "R30") (pin "1") (pinfunction "1_1") (pintype "passive"))
      (node (ref "R6") (pin "1") (pinfunction "1_1") (pintype "passive"))
      (node (ref "U3") (pin "3") (pinfunction "1IN+_3") (pintype "input"))
    )
    (net (code "30") (name "Net-(U3-1IN-)") (class "Default")
      (node (ref "C17") (pin "2") (pinfunction "2_2") (pintype "passive"))
      (node (ref "R20") (pin "2") (pinfunction "2_2") (pintype "passive"))
      (node (ref "R24") (pin "1") (pinfunction "1_1") (pintype "passive"))
      (node (ref "R31") (pin "1") (pinfunction "1_1") (pintype "passive"))
      (node (ref "R9") (pin "1") (pinfunction "1_1") (pintype "passive"))
      (node (ref "U3") (pin "4") (pinfunction "1IN-_4") (pintype "input"))
    )
    (net (code "31") (name "Net-(U3-1OUT)") (class "Default")
      (node (ref "C17") (pin "1") (pinfunction "1_1") (pintype "passive"))
      (node (ref "R13") (pin "1") (pinfunction "1_1") (pintype "passive"))
      (node (ref "R20") (pin "1") (pinfunction "1_1") (pintype "passive"))
      (node (ref "R32") (pin "2") (pinfunction "2_2") (pintype "passive"))
      (node (ref "U3") (pin "1") (pinfunction "1OUT_1") (pintype "output"))
    )
    (net (code "32") (name "Net-(U5-IN+)") (class "Default")
      (node (ref "C4") (pin "2") (pinfunction "2_2") (pintype "passive"))
      (node (ref "R17") (pin "2") (pinfunction "2_2") (pintype "passive"))
      (node (ref "R22") (pin "1") (pinfunction "1_1") (pintype "passive"))
      (node (ref "U5") (pin "3") (pinfunction "IN+_3") (pintype "input"))
    )
    (net (code "33") (name "Net-(U8-1IN+)") (class "Default")
      (node (ref "C28") (pin "2") (pinfunction "2_2") (pintype "passive"))
      (node (ref "C8") (pin "2") (pinfunction "2_2") (pintype "passive"))
      (node (ref "R21") (pin "1") (pinfunction "1_1") (pintype "passive"))
      (node (ref "R32") (pin "1") (pinfunction "1_1") (pintype "passive"))
      (node (ref "U8") (pin "3") (pinfunction "1IN+_3") (pintype "input"))
    )
    (net (code "34") (name "Net-(U8-1IN-)") (class "Default")
      (node (ref "C23") (pin "2") (pinfunction "2_2") (pintype "passive"))
      (node (ref "R14") (pin "1") (pinfunction "1_1") (pintype "passive"))
      (node (ref "R16") (pin "1") (pinfunction "1_1") (pintype "passive"))
      (node (ref "R18") (pin "1") (pinfunction "1_1") (pintype "passive"))
      (node (ref "R7") (pin "2") (pinfunction "2_2") (pintype "passive"))
      (node (ref "U8") (pin "4") (pinfunction "1IN-_4") (pintype "input"))
    )
    (net (code "35") (name "Net-(U8-1OUT)") (class "Default")
      (node (ref "C23") (pin "1") (pinfunction "1_1") (pintype "passive"))
      (node (ref "R11") (pin "1") (pinfunction "1_1") (pintype "passive"))
      (node (ref "R15") (pin "2") (pinfunction "2_2") (pintype "passive"))
      (node (ref "R4") (pin "2") (pinfunction "2_2") (pintype "passive"))
      (node (ref "R8") (pin "2") (pinfunction "2_2") (pintype "passive"))
      (node (ref "U8") (pin "1") (pinfunction "1OUT_1") (pintype "output"))
    )
  )
)
